# Schemamicro2.net
KiCad netlist of a schematic drawn in Altium Designer
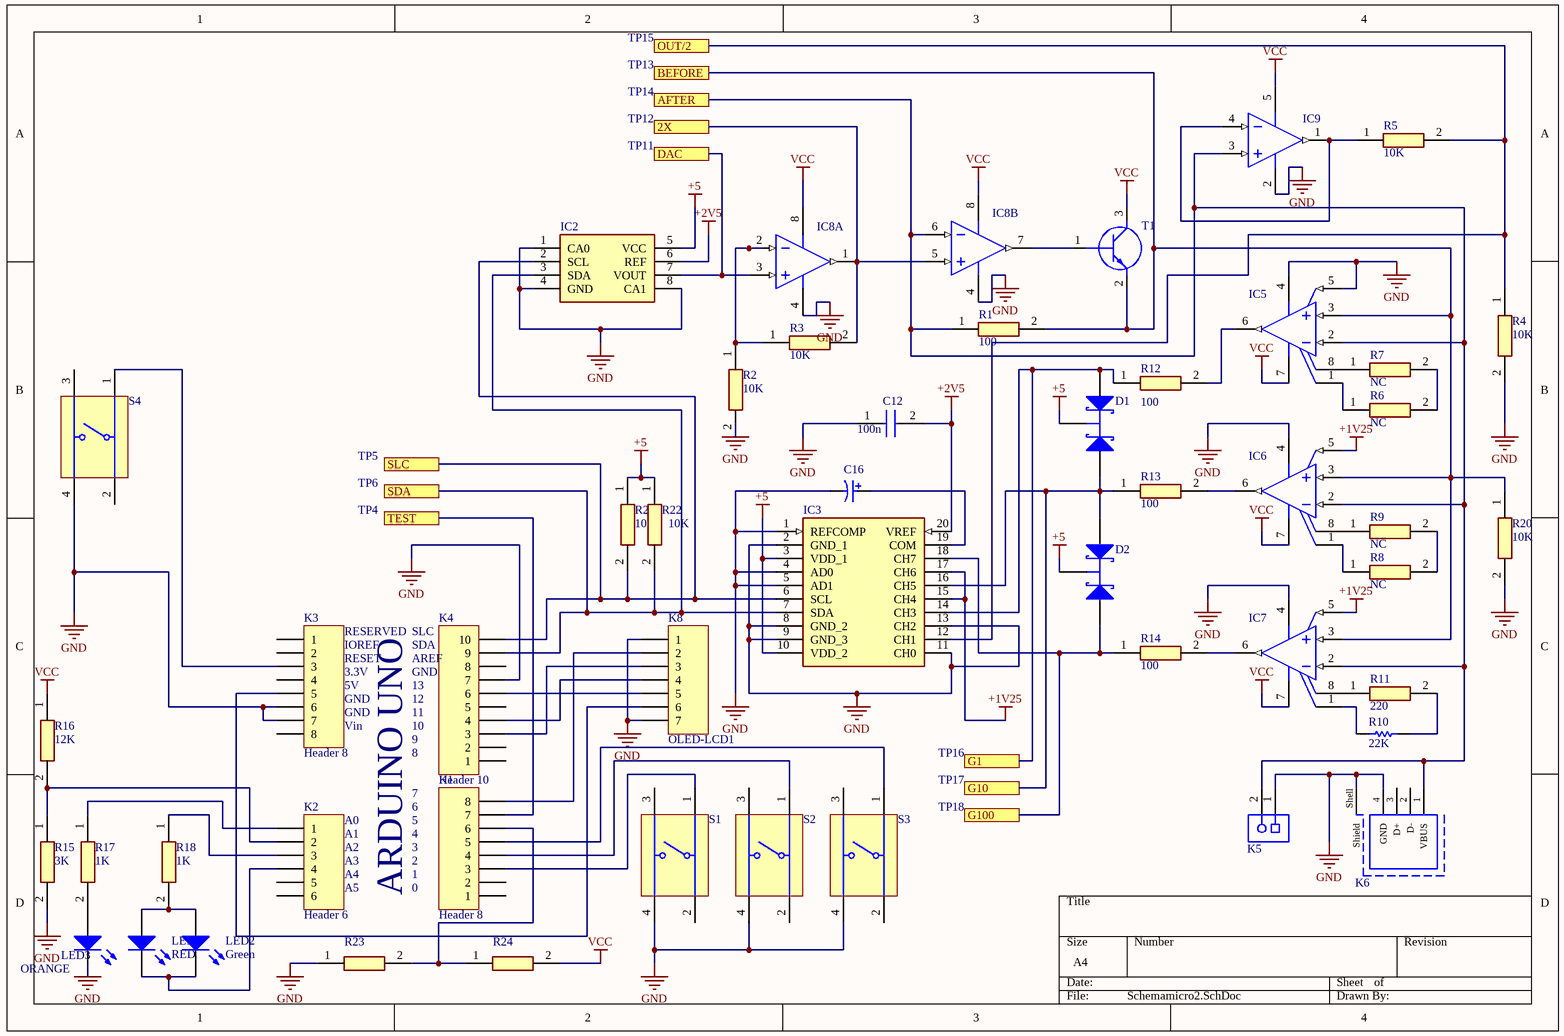
[diagram p0: Schemamicro2.SchDoc]

(export (version "E")
  (design (tool "Eeschema 10.0.6"))
  (components
    (comp (ref "C12")
      (value "100n")
      (footprint "SamacSys:CAPC2012X90N")
      (description "Capacitor")
      (fields (field (name "MANUFACTURER_PART_NUMBER") "MC0805B104K500CT"))
      (libsource (lib "*") (part "MC0805B104K500CT"))
    )
    (comp (ref "C16")
      (value "~")
      (footprint "KEMT-T491-B_L")
      (fields (field (name "MANUFACTURER") "Kemet") (field (name "VOLTAGE") "16VDC"))
      (libsource (lib "Altium Content Vault") (part "CAP-P-2"))
    )
    (comp (ref "D1")
      (value "~")
      (footprint "NXP-SOT23-3_V")
      (description "Schottky Barrier Diode, 30 V, 2 uA, -55 to 150 degC, 3-Pin SOT23, RoHS, Tape and Reel")
      (fields (field (name "PARTNUMBER") "BAT54C") (field (name "MANUFACTURER") "NXP Semiconductors"))
      (libsource (lib "Altium Content Vault") (part "NXP-DSKY_A1A2K3-3"))
    )
    (comp (ref "D2")
      (value "~")
      (footprint "NXP-SOT23-3_V")
      (description "Schottky Barrier Diode, 30 V, 2 uA, -55 to 150 degC, 3-Pin SOT23, RoHS, Tape and Reel")
      (fields (field (name "PARTNUMBER") "BAT54C") (field (name "MANUFACTURER") "NXP Semiconductors"))
      (libsource (lib "Altium Content Vault") (part "NXP-DSKY_A1A2K3-3"))
    )
    (comp (ref "IC2")
      (value "~")
      (footprint "SamacSys:SOT65P280X100-8N")
      (description "Integrated Circuit")
      (fields
        (field (name "MANUFACTURER_PART_NUMBER") "LTC2631CTS8-LZ12#TRMPBF")
        (field (name "MOUSER PART NUMBER") "584-2631CTS8LZ12TMPF")
      )
      (libsource (lib "*") (part "LTC2631CTS8-LZ12#TRMPBF"))
    )
    (comp (ref "IC3")
      (value "~")
      (footprint "SamacSys:SOP65P640X110-20N")
      (description "Integrated Circuit")
      (fields
        (field (name "MANUFACTURER_PART_NUMBER") "LTC2309CF#PBF")
        (field (name "MOUSER PART NUMBER") "584-LTC2309CF#PBF")
      )
      (libsource (lib "*") (part "LTC2309CF#PBF"))
    )
    (comp (ref "IC5")
      (value "~")
      (footprint "LT-S8-8_M")
      (fields
        (field (name "MANUFACTURER") "Linear Technology")
        (field (name "PARTNUMBER") "LT1789CS8-1#PBF")
        (field (name "LINEAR TECHNOLOGY PART NUMBER") "LT1789-1")
      )
      (libsource (lib "Altium Content Vault") (part "LT-LT1789-1-S8-8"))
    )
    (comp (ref "IC6")
      (value "~")
      (footprint "LT-S8-8_N")
      (fields
        (field (name "PARTNUMBER") "LT1789CS8-10#PBF")
        (field (name "MANUFACTURER") "Linear Technology")
        (field (name "LINEAR TECHNOLOGY PART NUMBER") "LT1789-10")
      )
      (libsource (lib "Altium Content Vault") (part "LT-LT1789-10-S8-8"))
    )
    (comp (ref "IC7")
      (value "~")
      (footprint "LT-S8-8_N")
      (fields
        (field (name "PARTNUMBER") "LT1789CS8-10#PBF")
        (field (name "MANUFACTURER") "Linear Technology")
        (field (name "LINEAR TECHNOLOGY PART NUMBER") "LT1789-10")
      )
      (libsource (lib "Altium Content Vault") (part "LT-LT1789-10-S8-8"))
    )
    (comp (ref "IC8")
      (value "~")
      (footprint "LT-S8-8_M")
      (fields
        (field (name "LINEAR TECHNOLOGY PART NUMBER") "LTC6241HV")
        (field (name "PARTNUMBER") "LTC6241HVCS8#PBF")
        (field (name "MANUFACTURER") "Linear Technology")
      )
      (libsource (lib "Altium Content Vault") (part "LT-LTC6241HV-S8-8"))
    )
    (comp (ref "IC9")
      (value "~")
      (footprint "LT-S5-5-TSOT-23_L")
      (fields
        (field (name "PARTNUMBER") "LTC2054HVCS5#TRMPBF")
        (field (name "LINEAR TECHNOLOGY PART NUMBER") "LTC2054HV")
        (field (name "MANUFACTURER") "Linear Technology")
      )
      (libsource (lib "Altium Content Vault") (part "LT-LT1395-LT18XX-LTC20XX-5"))
    )
    (comp (ref "K1")
      (value "Header 8")
      (footprint "HDR1X8")
      (description "Header, 8-Pin")
      (fields (field (name "PUBLISHER") "Altium Limited"))
      (libsource (lib "") (part "Header 8_1"))
    )
    (comp (ref "K2")
      (value "Header 6")
      (footprint "HDR1X6")
      (description "Header, 6-Pin")
      (fields (field (name "PUBLISHER") "Altium Limited"))
      (libsource (lib "Miscellaneous Connectors") (part "Header 6"))
    )
    (comp (ref "K3")
      (value "Header 8")
      (footprint "HDR1X8")
      (description "Header, 8-Pin")
      (fields (field (name "PUBLISHER") "Altium Limited"))
      (libsource (lib "Miscellaneous Connectors") (part "Header 8"))
    )
    (comp (ref "K4")
      (value "Header 10")
      (footprint "HDR1X10")
      (description "Header, 10-Pin")
      (fields (field (name "PUBLISHER") "Altium Limited"))
      (libsource (lib "Miscellaneous Connectors") (part "Header 10"))
    )
    (comp (ref "K5")
      (value "~")
      (footprint "PHOE-1729128-2_V")
      (description "PCB Terminal Block, 13.5 A, 400 V, 2-Pin THD, RoHS, Bulk")
      (fields (field (name "PARTNUMBER") "1729128") (field (name "MANUFACTURER") "Phoenix Contact"))
      (libsource (lib "Altium Content Vault") (part "CN-2P-F-R2"))
    )
    (comp (ref "K6")
      (value "~")
      (footprint "61400416021")
      (description "USB 2.0 Type A Receptacle WR-COM, Horizontal, THT")
      (fields
        (field (name "PART NUMBER") "61400416021")
        (field (name "MANUFACTURER") "Wurth Elektronik")
        (field (name "PUBLISHER") "WurthElektronik")
      )
      (libsource (lib "Altium Content Vault") (part "WE-USB-4-1SHLD"))
    )
    (comp (ref "K8")
      (value "OLED-LCD1")
      (footprint "HDR1X7")
      (description "Header, 7-Pin")
      (fields (field (name "PUBLISHER") "Altium Limited"))
      (libsource (lib "Miscellaneous Connectors") (part "Header 7"))
    )
    (comp (ref "LED1")
      (value "RED")
      (footprint "1206_A")
      (description "SMD mono-color Chip LED, WL-SMCW, Red")
      (fields (field (name "PARTNUMBER") "150120RS75000") (field (name "MANUFACTURER") "Wuerth Elektronik"))
      (libsource (lib "Altium Content Vault") (part "WE-LED_K1A2-2"))
    )
    (comp (ref "LED2")
      (value "Green")
      (footprint "1206_A")
      (description "SMD mono-color Chip LED, WL-SMCW, Green")
      (fields (field (name "MANUFACTURER") "Wuerth Elektronik") (field (name "PARTNUMBER") "150120GS75000"))
      (libsource (lib "Altium Content Vault") (part "WE-LED_K1A2-2"))
    )
    (comp (ref "LED3")
      (value "ORANGE")
      (footprint "1206_A")
      (description "SMD mono-color Chip LED, WL-SMCW, Yellow")
      (fields (field (name "PARTNUMBER") "150120YS75000") (field (name "MANUFACTURER") "Wuerth Elektronik"))
      (libsource (lib "Altium Content Vault") (part "WE-LED_K1A2-2"))
    )
    (comp (ref "R1")
      (value "100")
      (footprint "SamacSys:RESC2012X65N")
      (description "Resistor")
      (fields (field (name "MANUFACTURER_PART_NUMBER") "MCTC0525B1000T5E"))
      (libsource (lib "*") (part "MCTC0525B1000T5E"))
    )
    (comp (ref "R2")
      (value "10K")
      (footprint "SamacSys:RESC2012X65N")
      (description "Resistor")
      (fields (field (name "MANUFACTURER_PART_NUMBER") "MCTC0525B1002T5E"))
      (libsource (lib "*") (part "MCTC0525B1002T5E"))
    )
    (comp (ref "R3")
      (value "10K")
      (footprint "SamacSys:RESC2012X65N")
      (description "Resistor")
      (fields (field (name "MANUFACTURER_PART_NUMBER") "MCTC0525B1002T5E"))
      (libsource (lib "") (part "MCTC0525B1002T5E_1"))
    )
    (comp (ref "R4")
      (value "10K")
      (footprint "SamacSys:RESC2012X65N")
      (description "Resistor")
      (fields (field (name "MANUFACTURER_PART_NUMBER") "MCTC0525B1002T5E"))
      (libsource (lib "*") (part "MCTC0525B1002T5E"))
    )
    (comp (ref "R5")
      (value "10K")
      (footprint "SamacSys:RESC2012X65N")
      (description "Resistor")
      (fields (field (name "MANUFACTURER_PART_NUMBER") "MCTC0525B1002T5E"))
      (libsource (lib "") (part "MCTC0525B1002T5E_1"))
    )
    (comp (ref "R6")
      (value "NC")
      (footprint "SamacSys:RESC2012X65N")
      (description "Resistor")
      (fields (field (name "MANUFACTURER_PART_NUMBER") "MCTC0525B1000T5E"))
      (libsource (lib "*") (part "MCTC0525B1000T5E"))
    )
    (comp (ref "R7")
      (value "NC")
      (footprint "SamacSys:RESC2012X65N")
      (description "Resistor")
      (fields (field (name "MANUFACTURER_PART_NUMBER") "MCTC0525B1000T5E"))
      (libsource (lib "*") (part "MCTC0525B1000T5E"))
    )
    (comp (ref "R8")
      (value "NC")
      (footprint "SamacSys:RESC2012X65N")
      (description "Resistor")
      (fields (field (name "MANUFACTURER_PART_NUMBER") "MCTC0525B1000T5E"))
      (libsource (lib "*") (part "MCTC0525B1000T5E"))
    )
    (comp (ref "R9")
      (value "NC")
      (footprint "SamacSys:RESC2012X65N")
      (description "Resistor")
      (fields (field (name "MANUFACTURER_PART_NUMBER") "MCTC0525B1000T5E"))
      (libsource (lib "*") (part "MCTC0525B1000T5E"))
    )
    (comp (ref "R10")
      (value "22K")
      (footprint "RESC2013X60X40ML20T25")
      (fields (field (name "MANUFACTURER") "Panasonic") (field (name "PART NUMBER") "ERA6AEB223V"))
      (libsource (lib "Altium Content Vault") (part "RES"))
    )
    (comp (ref "R11")
      (value "220")
      (footprint "SamacSys:RESC2012X65N")
      (description "Resistor 220 ohm")
      (fields (field (name "MANUFACTURER_PART_NUMBER") "MCTC0525B1000T5E"))
      (libsource (lib "*") (part "MCTC0525B1000T5E"))
    )
    (comp (ref "R12")
      (value "100")
      (footprint "SamacSys:RESC2014X65N")
      (description "Resistor")
      (fields (field (name "MANUFACTURER_PART_NUMBER") "MC01W08055100R"))
      (libsource (lib "SamacSys") (part "MC01W08055100R"))
    )
    (comp (ref "R13")
      (value "100")
      (footprint "SamacSys:RESC2014X65N")
      (description "Resistor")
      (fields (field (name "MANUFACTURER_PART_NUMBER") "MC01W08055100R"))
      (libsource (lib "SamacSys") (part "MC01W08055100R"))
    )
    (comp (ref "R14")
      (value "100")
      (footprint "SamacSys:RESC2014X65N")
      (description "Resistor")
      (fields (field (name "MANUFACTURER_PART_NUMBER") "MC01W08055100R"))
      (libsource (lib "SamacSys") (part "MC01W08055100R"))
    )
    (comp (ref "R15")
      (value "3K")
      (footprint "SamacSys:RESC2014X65N")
      (description "Resistor")
      (fields (field (name "MANUFACTURER_PART_NUMBER") "MC01W0805512K"))
      (libsource (lib "SamacSys") (part "MC01W0805512K"))
    )
    (comp (ref "R16")
      (value "12K")
      (footprint "SamacSys:RESC2014X65N")
      (description "Resistor")
      (fields (field (name "MANUFACTURER_PART_NUMBER") "MC01W0805512K"))
      (libsource (lib "SamacSys") (part "MC01W0805512K"))
    )
    (comp (ref "R17")
      (value "1K")
      (footprint "SamacSys:RESC2014X65N")
      (description "Resistor 1K ohm")
      (fields (field (name "MANUFACTURER_PART_NUMBER") "MC01W080551K"))
      (libsource (lib "*") (part "MC01W080551K"))
    )
    (comp (ref "R18")
      (value "1K")
      (footprint "SamacSys:RESC2014X65N")
      (description "Resistor 1K ohm")
      (fields (field (name "MANUFACTURER_PART_NUMBER") "MC01W080551K"))
      (libsource (lib "*") (part "MC01W080551K"))
    )
    (comp (ref "R20")
      (value "10K")
      (footprint "SamacSys:RESC2014X65N")
      (description "Resistor")
      (fields (field (name "MANUFACTURER_PART_NUMBER") "MC01W0805510K"))
      (libsource (lib "SamacSys") (part "MC01W0805510K"))
    )
    (comp (ref "R21")
      (value "10K")
      (footprint "SamacSys:RESC2014X65N")
      (description "Resistor")
      (fields (field (name "MANUFACTURER_PART_NUMBER") "MC01W0805510K"))
      (libsource (lib "SamacSys") (part "MC01W0805510K"))
    )
    (comp (ref "R22")
      (value "10K")
      (footprint "SamacSys:RESC2014X65N")
      (description "Resistor")
      (fields (field (name "MANUFACTURER_PART_NUMBER") "MC01W0805510K"))
      (libsource (lib "SamacSys") (part "MC01W0805510K"))
    )
    (comp (ref "R23")
      (value "~")
      (footprint "SamacSys:RESC2014X65N")
      (description "Resistor")
      (fields (field (name "MANUFACTURER_PART_NUMBER") "MC01W0805510K"))
      (libsource (lib "") (part "MC01W0805510K_1"))
    )
    (comp (ref "R24")
      (value "~")
      (footprint "SamacSys:RESC2014X65N")
      (description "Resistor")
      (fields (field (name "MANUFACTURER_PART_NUMBER") "MC01W0805510K"))
      (libsource (lib "") (part "MC01W0805510K_1"))
    )
    (comp (ref "S1")
      (value "~")
      (footprint "TECO-1825910-6_V")
      (description "Tact Switch, SPST-NO, 0.05 A, -35 to 85 degC, 4-Pin THD, RoHS, Bulk")
      (fields (field (name "PART NO") "1825910-6") (field (name "MANUFACTURER") "TE Connectivity"))
      (libsource (lib "Altium Content Vault") (part "SW-SPST-4_A"))
    )
    (comp (ref "S2")
      (value "~")
      (footprint "TECO-1825910-6_V")
      (description "Tact Switch, SPST-NO, 0.05 A, -35 to 85 degC, 4-Pin THD, RoHS, Bulk")
      (fields (field (name "PART NO") "1825910-6") (field (name "MANUFACTURER") "TE Connectivity"))
      (libsource (lib "Altium Content Vault") (part "SW-SPST-4_A"))
    )
    (comp (ref "S3")
      (value "~")
      (footprint "TECO-1825910-6_V")
      (description "Tact Switch, SPST-NO, 0.05 A, -35 to 85 degC, 4-Pin THD, RoHS, Bulk")
      (fields (field (name "PART NO") "1825910-6") (field (name "MANUFACTURER") "TE Connectivity"))
      (libsource (lib "Altium Content Vault") (part "SW-SPST-4_A"))
    )
    (comp (ref "S4")
      (value "~")
      (footprint "TECO-1825910-6_V")
      (description "Tact Switch, SPST-NO, 0.05 A, -35 to 85 degC, 4-Pin THD, RoHS, Bulk")
      (fields (field (name "PART NO") "1825910-6") (field (name "MANUFACTURER") "TE Connectivity"))
      (libsource (lib "Altium Content Vault") (part "SW-SPST-4_A"))
    )
    (comp (ref "T1")
      (value "~")
      (footprint "SamacSys:SOT95P230X110-3N")
      (description "Transistor BJT NPN")
      (fields (field (name "MANUFACTURER_PART_NUMBER") "BC847C/AU,215"))
      (libsource (lib "*") (part "BC847C_AU,215"))
    )
  )
  (nets
    (net (code "1") (name "+1V25") (class "Default")
      (node (ref "IC3") (pin "15") (pinfunction "CH4_15") (pintype "passive"))
      (node (ref "IC3") (pin "17") (pinfunction "CH6_17") (pintype "passive"))
      (node (ref "IC6") (pin "5") (pinfunction "REF_5") (pintype "input"))
      (node (ref "IC7") (pin "5") (pinfunction "REF_5") (pintype "input"))
    )
    (net (code "2") (name "+2V5") (class "Default")
      (node (ref "C12") (pin "2") (pinfunction "2_2") (pintype "passive"))
      (node (ref "IC2") (pin "6") (pinfunction "REF_6") (pintype "passive"))
      (node (ref "IC3") (pin "20") (pinfunction "VREF_20") (pintype "input"))
    )
    (net (code "3") (name "+5") (class "Default")
      (node (ref "D1") (pin "3") (pinfunction "K_3") (pintype "passive"))
      (node (ref "D2") (pin "3") (pinfunction "K_3") (pintype "passive"))
      (node (ref "IC2") (pin "5") (pinfunction "VCC_5") (pintype "passive"))
      (node (ref "IC3") (pin "10") (pinfunction "VDD_2_10") (pintype "power_in"))
      (node (ref "IC3") (pin "3") (pinfunction "VDD_1_3") (pintype "power_in"))
      (node (ref "R21") (pin "1") (pinfunction "1_1") (pintype "passive"))
      (node (ref "R22") (pin "1") (pinfunction "1_1") (pintype "passive"))
    )
    (net (code "4") (name "/2X") (class "Default")
      (node (ref "IC8") (pin "1") (pinfunction "OUT_A_1") (pintype "output"))
      (node (ref "IC8") (pin "5") (pinfunction "+IN_B_5") (pintype "input"))
      (node (ref "R3") (pin "2") (pinfunction "2_2") (pintype "passive"))
    )
    (net (code "5") (name "/AFTER") (class "Default")
      (node (ref "IC5") (pin "2") (pinfunction "-IN_2") (pintype "input"))
      (node (ref "IC6") (pin "2") (pinfunction "-IN_2") (pintype "input"))
      (node (ref "IC7") (pin "2") (pinfunction "-IN_2") (pintype "input"))
      (node (ref "IC8") (pin "6") (pinfunction "-IN_B_6") (pintype "input"))
      (node (ref "IC9") (pin "3") (pinfunction "+IN_3") (pintype "input"))
      (node (ref "K5") (pin "2") (pinfunction "2_2") (pintype "passive"))
      (node (ref "K6") (pin "1") (pinfunction "VBUS_1") (pintype "passive"))
      (node (ref "R1") (pin "1") (pinfunction "1_1") (pintype "passive"))
    )
    (net (code "6") (name "/BEFORE") (class "Default")
      (node (ref "IC5") (pin "3") (pinfunction "+IN_3") (pintype "input"))
      (node (ref "IC6") (pin "3") (pinfunction "+IN_3") (pintype "input"))
      (node (ref "IC7") (pin "3") (pinfunction "+IN_3") (pintype "input"))
      (node (ref "R1") (pin "2") (pinfunction "2_2") (pintype "passive"))
      (node (ref "R20") (pin "1") (pinfunction "1_1") (pintype "passive"))
      (node (ref "T1") (pin "2") (pinfunction "E_2") (pintype "passive"))
    )
    (net (code "7") (name "/DAC") (class "Default")
      (node (ref "IC2") (pin "7") (pinfunction "VOUT_7") (pintype "passive"))
      (node (ref "IC8") (pin "3") (pinfunction "+IN_A_3") (pintype "input"))
    )
    (net (code "8") (name "/G1") (class "Default")
      (node (ref "D1") (pin "2") (pinfunction "A_2") (pintype "passive"))
      (node (ref "IC3") (pin "14") (pinfunction "CH3_14") (pintype "passive"))
      (node (ref "R12") (pin "1") (pinfunction "1_1") (pintype "passive"))
    )
    (net (code "9") (name "/G10") (class "Default")
      (node (ref "D1") (pin "1") (pinfunction "A_1") (pintype "passive"))
      (node (ref "D2") (pin "2") (pinfunction "A_2") (pintype "passive"))
      (node (ref "IC3") (pin "16") (pinfunction "CH5_16") (pintype "passive"))
      (node (ref "R13") (pin "1") (pinfunction "1_1") (pintype "passive"))
    )
    (net (code "10") (name "/G100") (class "Default")
      (node (ref "D2") (pin "1") (pinfunction "A_1") (pintype "passive"))
      (node (ref "IC3") (pin "18") (pinfunction "CH7_18") (pintype "passive"))
      (node (ref "R14") (pin "1") (pinfunction "1_1") (pintype "passive"))
    )
    (net (code "11") (name "/OUT{slash}2") (class "Default")
      (node (ref "IC3") (pin "12") (pinfunction "CH1_12") (pintype "passive"))
      (node (ref "R4") (pin "1") (pinfunction "1_1") (pintype "passive"))
      (node (ref "R5") (pin "2") (pinfunction "2_2") (pintype "passive"))
    )
    (net (code "12") (name "/SDA") (class "Default")
      (node (ref "IC2") (pin "3") (pinfunction "SDA_3") (pintype "passive"))
      (node (ref "IC3") (pin "7") (pinfunction "SDA_7") (pintype "passive"))
      (node (ref "K4") (pin "9") (pinfunction "9_9") (pintype "passive"))
      (node (ref "R22") (pin "2") (pinfunction "2_2") (pintype "passive"))
    )
    (net (code "13") (name "/SLC") (class "Default")
      (node (ref "IC2") (pin "2") (pinfunction "SCL_2") (pintype "passive"))
      (node (ref "IC3") (pin "6") (pinfunction "SCL_6") (pintype "passive"))
      (node (ref "K4") (pin "10") (pinfunction "10_10") (pintype "passive"))
      (node (ref "R21") (pin "2") (pinfunction "2_2") (pintype "passive"))
    )
    (net (code "14") (name "/TEST") (class "Default")
      (node (ref "K1") (pin "7") (pinfunction "7_7") (pintype "passive"))
    )
    (net (code "15") (name "GND") (class "Default")
      (node (ref "C12") (pin "1") (pinfunction "1_1") (pintype "passive"))
      (node (ref "C16") (pin "2") (pinfunction "2_2") (pintype "passive"))
      (node (ref "IC2") (pin "1") (pinfunction "CA0_1") (pintype "passive"))
      (node (ref "IC2") (pin "4") (pinfunction "GND_4") (pintype "passive"))
      (node (ref "IC2") (pin "8") (pinfunction "CA1_8") (pintype "passive"))
      (node (ref "IC3") (pin "1") (pinfunction "REFCOMP_1") (pintype "input"))
      (node (ref "IC3") (pin "11") (pinfunction "CH0_11") (pintype "passive"))
      (node (ref "IC3") (pin "13") (pinfunction "CH2_13") (pintype "passive"))
      (node (ref "IC3") (pin "2") (pinfunction "GND_1_2") (pintype "power_in"))
      (node (ref "IC3") (pin "4") (pinfunction "AD0_4") (pintype "passive"))
      (node (ref "IC3") (pin "5") (pinfunction "AD1_5") (pintype "passive"))
      (node (ref "IC3") (pin "8") (pinfunction "GND_2_8") (pintype "power_in"))
      (node (ref "IC3") (pin "9") (pinfunction "GND_3_9") (pintype "power_in"))
      (node (ref "IC5") (pin "4") (pinfunction "-VS_4") (pintype "power_in"))
      (node (ref "IC5") (pin "5") (pinfunction "REF_5") (pintype "input"))
      (node (ref "IC6") (pin "4") (pinfunction "-VS_4") (pintype "power_in"))
      (node (ref "IC7") (pin "4") (pinfunction "-VS_4") (pintype "power_in"))
      (node (ref "IC8") (pin "4") (pinfunction "V-_4") (pintype "power_in"))
      (node (ref "IC9") (pin "2") (pinfunction "V-_2") (pintype "power_in"))
      (node (ref "K3") (pin "6") (pinfunction "6_6") (pintype "passive"))
      (node (ref "K3") (pin "7") (pinfunction "7_7") (pintype "passive"))
      (node (ref "K4") (pin "7") (pinfunction "7_7") (pintype "passive"))
      (node (ref "K5") (pin "1") (pinfunction "1_1") (pintype "passive"))
      (node (ref "K6") (pin "4") (pinfunction "GND_4") (pintype "passive"))
      (node (ref "K6") (pin "Shell") (pinfunction "Shield_Shell") (pintype "passive"))
      (node (ref "K8") (pin "1") (pinfunction "1_1") (pintype "passive"))
      (node (ref "K8") (pin "7") (pinfunction "7_7") (pintype "passive"))
      (node (ref "LED3") (pin "1") (pinfunction "K_1") (pintype "passive"))
      (node (ref "R15") (pin "2") (pinfunction "2_2") (pintype "passive"))
      (node (ref "R2") (pin "2") (pinfunction "2_2") (pintype "passive"))
      (node (ref "R20") (pin "2") (pinfunction "2_2") (pintype "passive"))
      (node (ref "R23") (pin "1") (pinfunction "1_1") (pintype "passive"))
      (node (ref "R4") (pin "2") (pinfunction "2_2") (pintype "passive"))
      (node (ref "S1") (pin "4") (pinfunction "4_4") (pintype "passive"))
      (node (ref "S2") (pin "4") (pinfunction "4_4") (pintype "passive"))
      (node (ref "S3") (pin "4") (pinfunction "4_4") (pintype "passive"))
      (node (ref "S4") (pin "4") (pinfunction "4_4") (pintype "passive"))
    )
    (net (code "16") (name "Net-(IC3-COM)") (class "Default")
      (node (ref "C16") (pin "1") (pinfunction "1_1") (pintype "passive"))
      (node (ref "IC3") (pin "19") (pinfunction "COM_19") (pintype "passive"))
    )
    (net (code "17") (name "Net-(IC5-OUT)") (class "Default")
      (node (ref "IC5") (pin "6") (pinfunction "OUT_6") (pintype "output"))
      (node (ref "R12") (pin "2") (pinfunction "2_2") (pintype "passive"))
    )
    (net (code "18") (name "Net-(IC5-RG-Pad1)") (class "Default")
      (node (ref "IC5") (pin "1") (pinfunction "RG_1") (pintype "passive"))
      (node (ref "R6") (pin "1") (pinfunction "1_1") (pintype "passive"))
    )
    (net (code "19") (name "Net-(IC5-RG-Pad8)") (class "Default")
      (node (ref "IC5") (pin "8") (pinfunction "RG_8") (pintype "passive"))
      (node (ref "R7") (pin "1") (pinfunction "1_1") (pintype "passive"))
    )
    (net (code "20") (name "Net-(IC6-OUT)") (class "Default")
      (node (ref "IC6") (pin "6") (pinfunction "OUT_6") (pintype "output"))
      (node (ref "R13") (pin "2") (pinfunction "2_2") (pintype "passive"))
    )
    (net (code "21") (name "Net-(IC6-RG-Pad1)") (class "Default")
      (node (ref "IC6") (pin "1") (pinfunction "RG_1") (pintype "passive"))
      (node (ref "R8") (pin "1") (pinfunction "1_1") (pintype "passive"))
    )
    (net (code "22") (name "Net-(IC6-RG-Pad8)") (class "Default")
      (node (ref "IC6") (pin "8") (pinfunction "RG_8") (pintype "passive"))
      (node (ref "R9") (pin "1") (pinfunction "1_1") (pintype "passive"))
    )
    (net (code "23") (name "Net-(IC7-OUT)") (class "Default")
      (node (ref "IC7") (pin "6") (pinfunction "OUT_6") (pintype "output"))
      (node (ref "R14") (pin "2") (pinfunction "2_2") (pintype "passive"))
    )
    (net (code "24") (name "Net-(IC7-RG-Pad1)") (class "Default")
      (node (ref "IC7") (pin "1") (pinfunction "RG_1") (pintype "passive"))
      (node (ref "R10") (pin "1") (pinfunction "1_1") (pintype "passive"))
    )
    (net (code "25") (name "Net-(IC7-RG-Pad8)") (class "Default")
      (node (ref "IC7") (pin "8") (pinfunction "RG_8") (pintype "passive"))
      (node (ref "R11") (pin "1") (pinfunction "1_1") (pintype "passive"))
    )
    (net (code "26") (name "Net-(IC8A--IN_A)") (class "Default")
      (node (ref "IC8") (pin "2") (pinfunction "-IN_A_2") (pintype "input"))
      (node (ref "R2") (pin "1") (pinfunction "1_1") (pintype "passive"))
      (node (ref "R3") (pin "1") (pinfunction "1_1") (pintype "passive"))
    )
    (net (code "27") (name "Net-(IC8B-OUT_B)") (class "Default")
      (node (ref "IC8") (pin "7") (pinfunction "OUT_B_7") (pintype "output"))
      (node (ref "T1") (pin "1") (pinfunction "B_1") (pintype "passive"))
    )
    (net (code "28") (name "Net-(IC9--IN)") (class "Default")
      (node (ref "IC9") (pin "1") (pinfunction "OUT_1") (pintype "output"))
      (node (ref "IC9") (pin "4") (pinfunction "-IN_4") (pintype "input"))
      (node (ref "R5") (pin "1") (pinfunction "1_1") (pintype "passive"))
    )
    (net (code "29") (name "Net-(K1-Pad3)") (class "Default")
      (node (ref "K1") (pin "3") (pinfunction "3_3") (pintype "passive"))
      (node (ref "S1") (pin "1") (pinfunction "1_1") (pintype "passive"))
    )
    (net (code "30") (name "Net-(K1-Pad4)") (class "Default")
      (node (ref "K1") (pin "4") (pinfunction "4_4") (pintype "passive"))
      (node (ref "S2") (pin "1") (pinfunction "1_1") (pintype "passive"))
    )
    (net (code "31") (name "Net-(K1-Pad5)") (class "Default")
      (node (ref "K1") (pin "5") (pinfunction "5_5") (pintype "passive"))
      (node (ref "S3") (pin "1") (pinfunction "1_1") (pintype "passive"))
    )
    (net (code "32") (name "Net-(K1-Pad6)") (class "Default")
      (node (ref "K1") (pin "6") (pinfunction "6_6") (pintype "passive"))
      (node (ref "R23") (pin "2") (pinfunction "2_2") (pintype "passive"))
      (node (ref "R24") (pin "1") (pinfunction "1_1") (pintype "passive"))
    )
    (net (code "33") (name "Net-(K1-Pad8)") (class "Default")
      (node (ref "K1") (pin "8") (pinfunction "8_8") (pintype "passive"))
      (node (ref "K8") (pin "2") (pinfunction "2_2") (pintype "passive"))
    )
    (net (code "34") (name "Net-(K2-Pad1)") (class "Default")
      (node (ref "K2") (pin "1") (pinfunction "1_1") (pintype "passive"))
      (node (ref "R17") (pin "1") (pinfunction "1_1") (pintype "passive"))
    )
    (net (code "35") (name "Net-(K2-Pad2)") (class "Default")
      (node (ref "K2") (pin "2") (pinfunction "2_2") (pintype "passive"))
      (node (ref "R15") (pin "1") (pinfunction "1_1") (pintype "passive"))
      (node (ref "R16") (pin "2") (pinfunction "2_2") (pintype "passive"))
    )
    (net (code "36") (name "Net-(K2-Pad3)") (class "Default")
      (node (ref "K2") (pin "3") (pinfunction "3_3") (pintype "passive"))
      (node (ref "R18") (pin "1") (pinfunction "1_1") (pintype "passive"))
    )
    (net (code "37") (name "Net-(K3-Pad3)") (class "Default")
      (node (ref "K3") (pin "3") (pinfunction "3_3") (pintype "passive"))
      (node (ref "S4") (pin "1") (pinfunction "1_1") (pintype "passive"))
    )
    (net (code "38") (name "Net-(K3-Pad5)") (class "Default")
      (node (ref "K3") (pin "5") (pinfunction "5_5") (pintype "passive"))
      (node (ref "K8") (pin "6") (pinfunction "6_6") (pintype "passive"))
    )
    (net (code "39") (name "Net-(K4-Pad3)") (class "Default")
      (node (ref "K4") (pin "3") (pinfunction "3_3") (pintype "passive"))
      (node (ref "K8") (pin "3") (pinfunction "3_3") (pintype "passive"))
    )
    (net (code "40") (name "Net-(K4-Pad4)") (class "Default")
      (node (ref "K4") (pin "4") (pinfunction "4_4") (pintype "passive"))
      (node (ref "K8") (pin "4") (pinfunction "4_4") (pintype "passive"))
    )
    (net (code "41") (name "Net-(K4-Pad6)") (class "Default")
      (node (ref "K4") (pin "6") (pinfunction "6_6") (pintype "passive"))
      (node (ref "K8") (pin "5") (pinfunction "5_5") (pintype "passive"))
    )
    (net (code "42") (name "Net-(LED1-A)") (class "Default")
      (node (ref "LED1") (pin "2") (pinfunction "A_2") (pintype "passive"))
      (node (ref "LED2") (pin "2") (pinfunction "A_2") (pintype "passive"))
      (node (ref "R18") (pin "2") (pinfunction "2_2") (pintype "passive"))
    )
    (net (code "43") (name "Net-(LED1-K)") (class "Default")
      (node (ref "K2") (pin "4") (pinfunction "4_4") (pintype "passive"))
      (node (ref "LED1") (pin "1") (pinfunction "K_1") (pintype "passive"))
      (node (ref "LED2") (pin "1") (pinfunction "K_1") (pintype "passive"))
    )
    (net (code "44") (name "Net-(LED3-A)") (class "Default")
      (node (ref "LED3") (pin "2") (pinfunction "A_2") (pintype "passive"))
      (node (ref "R17") (pin "2") (pinfunction "2_2") (pintype "passive"))
    )
    (net (code "45") (name "Net-(R6-Pad2)") (class "Default")
      (node (ref "R6") (pin "2") (pinfunction "2_2") (pintype "passive"))
      (node (ref "R7") (pin "2") (pinfunction "2_2") (pintype "passive"))
    )
    (net (code "46") (name "Net-(R8-Pad2)") (class "Default")
      (node (ref "R8") (pin "2") (pinfunction "2_2") (pintype "passive"))
      (node (ref "R9") (pin "2") (pinfunction "2_2") (pintype "passive"))
    )
    (net (code "47") (name "Net-(R10-Pad2)") (class "Default")
      (node (ref "R10") (pin "2") (pinfunction "2_2") (pintype "passive"))
      (node (ref "R11") (pin "2") (pinfunction "2_2") (pintype "passive"))
    )
    (net (code "48") (name "VCC") (class "Default")
      (node (ref "IC5") (pin "7") (pinfunction "+VS_7") (pintype "power_in"))
      (node (ref "IC6") (pin "7") (pinfunction "+VS_7") (pintype "power_in"))
      (node (ref "IC7") (pin "7") (pinfunction "+VS_7") (pintype "power_in"))
      (node (ref "IC8") (pin "8") (pinfunction "V+_8") (pintype "power_in"))
      (node (ref "IC9") (pin "5") (pinfunction "V+_5") (pintype "power_in"))
      (node (ref "R16") (pin "1") (pinfunction "1_1") (pintype "passive"))
      (node (ref "R24") (pin "2") (pinfunction "2_2") (pintype "passive"))
      (node (ref "T1") (pin "3") (pinfunction "C_3") (pintype "passive"))
    )
    (net (code "49") (name "unconnected-(K1-Pad1)") (class "Default")
      (node (ref "K1") (pin "1") (pinfunction "1_1") (pintype "passive"))
    )
    (net (code "50") (name "unconnected-(K1-Pad2)") (class "Default")
      (node (ref "K1") (pin "2") (pinfunction "2_2") (pintype "passive"))
    )
    (net (code "51") (name "unconnected-(K2-Pad5)") (class "Default")
      (node (ref "K2") (pin "5") (pinfunction "5_5") (pintype "passive"))
    )
    (net (code "52") (name "unconnected-(K2-Pad6)") (class "Default")
      (node (ref "K2") (pin "6") (pinfunction "6_6") (pintype "passive"))
    )
    (net (code "53") (name "unconnected-(K3-Pad1)") (class "Default")
      (node (ref "K3") (pin "1") (pinfunction "1_1") (pintype "passive"))
    )
    (net (code "54") (name "unconnected-(K3-Pad2)") (class "Default")
      (node (ref "K3") (pin "2") (pinfunction "2_2") (pintype "passive"))
    )
    (net (code "55") (name "unconnected-(K3-Pad4)") (class "Default")
      (node (ref "K3") (pin "4") (pinfunction "4_4") (pintype "passive"))
    )
    (net (code "56") (name "unconnected-(K3-Pad8)") (class "Default")
      (node (ref "K3") (pin "8") (pinfunction "8_8") (pintype "passive"))
    )
    (net (code "57") (name "unconnected-(K4-Pad1)") (class "Default")
      (node (ref "K4") (pin "1") (pinfunction "1_1") (pintype "passive"))
    )
    (net (code "58") (name "unconnected-(K4-Pad2)") (class "Default")
      (node (ref "K4") (pin "2") (pinfunction "2_2") (pintype "passive"))
    )
    (net (code "59") (name "unconnected-(K4-Pad5)") (class "Default")
      (node (ref "K4") (pin "5") (pinfunction "5_5") (pintype "passive"))
    )
    (net (code "60") (name "unconnected-(K4-Pad8)") (class "Default")
      (node (ref "K4") (pin "8") (pinfunction "8_8") (pintype "passive"))
    )
    (net (code "61") (name "unconnected-(K6-D+-Pad3)") (class "Default")
      (node (ref "K6") (pin "3") (pinfunction "D+_3") (pintype "passive"))
    )
    (net (code "62") (name "unconnected-(K6-D--Pad2)") (class "Default")
      (node (ref "K6") (pin "2") (pinfunction "D-_2") (pintype "passive"))
    )
    (net (code "63") (name "unconnected-(S1-Pad2)") (class "Default")
      (node (ref "S1") (pin "2") (pinfunction "2_2") (pintype "passive"))
    )
    (net (code "64") (name "unconnected-(S1-Pad3)") (class "Default")
      (node (ref "S1") (pin "3") (pinfunction "3_3") (pintype "passive"))
    )
    (net (code "65") (name "unconnected-(S2-Pad2)") (class "Default")
      (node (ref "S2") (pin "2") (pinfunction "2_2") (pintype "passive"))
    )
    (net (code "66") (name "unconnected-(S2-Pad3)") (class "Default")
      (node (ref "S2") (pin "3") (pinfunction "3_3") (pintype "passive"))
    )
    (net (code "67") (name "unconnected-(S3-Pad2)") (class "Default")
      (node (ref "S3") (pin "2") (pinfunction "2_2") (pintype "passive"))
    )
    (net (code "68") (name "unconnected-(S3-Pad3)") (class "Default")
      (node (ref "S3") (pin "3") (pinfunction "3_3") (pintype "passive"))
    )
    (net (code "69") (name "unconnected-(S4-Pad2)") (class "Default")
      (node (ref "S4") (pin "2") (pinfunction "2_2") (pintype "passive"))
    )
    (net (code "70") (name "unconnected-(S4-Pad3)") (class "Default")
      (node (ref "S4") (pin "3") (pinfunction "3_3") (pintype "passive"))
    )
  )
)
